# Main.net
KiCad netlist of a schematic drawn in Altium Designer
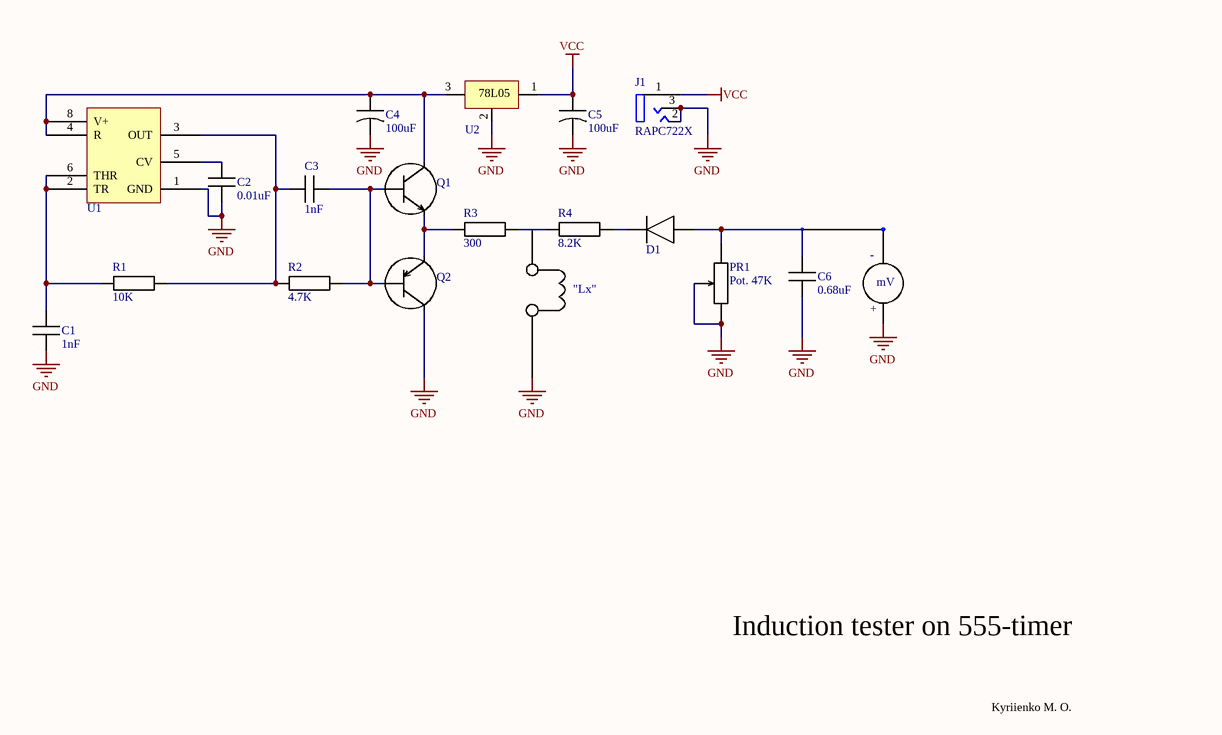
[diagram p0: Main.SchDoc]

(export (version "E")
  (design (tool "Eeschema 10.0.6"))
  (components
    (comp (ref "C1")
      (value "1nF")
      (footprint "Ceramica")
      (description "CAP CER 1000PF 1.5KV X7R RADIAL")
      (fields
        (field (name "MANUFACTURER") "KEMET")
        (field (name "MANUFACTURER PART NUMBER") "C322C102KFR5TA")
      )
      (libsource (lib "ComponentsLibrary") (part "C322C102KFR5TA"))
    )
    (comp (ref "C2")
      (value "0.01uF")
      (footprint "Ceramica")
      (description "Cap Ceramic 0.01uF 100V X7R 10% Radial 2.5mm 125C Bulk")
      (fields
        (field (name "MANUFACTURER") "Vishay BCcomponents")
        (field (name "MANUFACTURER PART NUMBER") "K103K15X7RH53L2")
      )
      (libsource (lib "ComponentsLibrary") (part "K103K15X7RH53L2"))
    )
    (comp (ref "C3")
      (value "1nF")
      (footprint "Ceramica")
      (description "CAP CER 1000PF 1.5KV X7R RADIAL")
      (fields
        (field (name "MANUFACTURER") "KEMET")
        (field (name "MANUFACTURER PART NUMBER") "C322C102KFR5TA")
      )
      (libsource (lib "ComponentsLibrary") (part "C322C102KFR5TA"))
    )
    (comp (ref "C4")
      (value "100uF")
      (footprint "Electrolytic")
      (description "Cap Aluminum Lytic 100uF 16V 20% (6.3 X 11mm) Radial 2.5mm 175mA 2000h 105C Ammo Pack")
      (fields
        (field (name "MANUFACTURER") "Nichicon")
        (field (name "MANUFACTURER PART NUMBER") "UPJ1C101MED1TD")
      )
      (libsource (lib "ComponentsLibrary") (part "UPJ1C101MED1TD"))
    )
    (comp (ref "C5")
      (value "100uF")
      (footprint "Electrolytic")
      (description "Cap Aluminum Lytic 100uF 16V 20% (6.3 X 11mm) Radial 2.5mm 175mA 2000h 105C Ammo Pack")
      (fields
        (field (name "MANUFACTURER") "Nichicon")
        (field (name "MANUFACTURER PART NUMBER") "UPJ1C101MED1TD")
      )
      (libsource (lib "ComponentsLibrary") (part "UPJ1C101MED1TD"))
    )
    (comp (ref "C6")
      (value "0.68uF")
      (footprint "Ceramica")
      (description "Capacitor Ceramic 0.68uF 50V X7R 10% 5mm Bulk")
      (fields
        (field (name "MANUFACTURER") "TDK")
        (field (name "MANUFACTURER PART NUMBER") "FA24X7R1H684KRU00")
      )
      (libsource (lib "ComponentsLibrary") (part "FA24X7R1H684KRU00"))
    )
    (comp (ref "D1")
      (value "Diode")
      (footprint "Diode")
      (description "Diode Ultra Fast Recovery Rectifier 100 Volt 0.3A 2-Pin DO-3")
      (fields
        (field (name "MANUFACTURER") "ON Semiconductor / Fairchild")
        (field (name "MANUFACTURER PART NUMBER") "1N4148")
      )
      (libsource (lib "ComponentsLibrary") (part "1N4148"))
    )
    (comp (ref "J1")
      (value "Conn_Switchcraft_RAPC722X_eec")
      (footprint "Switchcraft_RAPC722X_0")
      (description "CONN PWR JACK 2X5.5MM SOLDER")
      (fields
        (field (name "PART NUMBER") "RAPC722X")
        (field (name "MANUFACTURER") "Switchcraft")
        (field (name "MOUSER PART NUMBER") "502-RAPC722X")
      )
      (libsource (lib "Conn_Switchcraft_RAPC722X_eec") (part "Conn_Switchcraft_RAPC722X_eec"))
    )
    (comp (ref "PR1")
      (value "Pot. 47K")
      (footprint "Portentiometr")
      (description "Potentiometers 23E 47KA 10% 6.35X16FL B8")
      (fields
        (field (name "MANUFACTURER") "TE Connectivity")
        (field (name "MANUFACTURER PART NUMBER") "23ESA473KMF16N")
      )
      (libsource (lib "ComponentsLibrary") (part "23ESA473KMF16N"))
    )
    (comp (ref "Q1")
      (value "npn")
      (footprint "TO-92")
      (fields
        (field (name "MANUFACTURER") "ON Semiconductor / Fairchild")
        (field (name "MANUFACTURER PART NUMBER") "BC547B")
        (field (name "VOLTAGE") "40V")
      )
      (libsource (lib "ComponentsLibrary") (part "BC547B"))
    )
    (comp (ref "Q2")
      (value "pnp")
      (footprint "TO-92")
      (description "TRANS PNP 45V 0.2A TO-92")
      (fields
        (field (name "MANUFACTURER") "ON Semiconductor / Fairchild")
        (field (name "MANUFACTURER PART NUMBER") "KSA539YTA")
      )
      (libsource (lib "ComponentsLibrary") (part "KSA539YTA"))
    )
    (comp (ref "R1")
      (value "10K")
      (footprint "RESISTOR")
      (description "Carbon Film Resistors - Through Hole 10KOhm 1W 500PPM")
      (fields
        (field (name "MANUFACTURER") "TE Connectivity")
        (field (name "MANUFACTURER PART NUMBER") "CFR100J10K")
      )
      (libsource (lib "ComponentsLibrary") (part "CFR100J10K"))
    )
    (comp (ref "R2")
      (value "4.7K")
      (footprint "RESISTOR")
      (description "Res Carbon Film 4.7K Ohm 5% 0.25W(1/4W) -450ppm/C to 350ppm/C Conformal Coated AXL T/R")
      (fields
        (field (name "MANUFACTURER") "KOA Speer")
        (field (name "MANUFACTURER PART NUMBER") "CFS1/4CT52R472J")
      )
      (libsource (lib "ComponentsLibrary") (part "CFS1/4CT52R472J"))
    )
    (comp (ref "R3")
      (value "300")
      (footprint "RESISTOR")
      (description "RES 300 OHM 1W 5% AXIAL")
      (fields
        (field (name "MANUFACTURER") "Yageo")
        (field (name "MANUFACTURER PART NUMBER") "RSF100JB-73-300R")
      )
      (libsource (lib "ComponentsLibrary") (part "RSF100JB-73-300R"))
    )
    (comp (ref "R4")
      (value "8.2K")
      (footprint "RESISTOR")
      (description "RES 8.2K OHM 1/4W 5% AXIAL")
      (fields
        (field (name "MANUFACTURER") "Stackpole Electronics")
        (field (name "MANUFACTURER PART NUMBER") "CF14JA8K20")
      )
      (libsource (lib "ComponentsLibrary") (part "CF14JA8K20"))
    )
    (comp (ref "U1")
      (value "timer 555")
      (footprint "DIP8")
      (description "Standard Timer Single 8-Pin PDIP Tube")
      (fields
        (field (name "MANUFACTURER") "Texas Instruments")
        (field (name "MANUFACTURER PART NUMBER") "NE555P")
      )
      (libsource (lib "ComponentsLibrary") (part "NE555P"))
    )
    (comp (ref "U2")
      (value "78L05")
      (footprint "TO-92")
      (description "Standard Regulator Pos 5V 0.1A 3-Pin TO-92 Bag")
      (fields
        (field (name "MANUFACTURER") "STMicroelectronics")
        (field (name "MANUFACTURER PART NUMBER") "L78L05ACZ")
      )
      (libsource (lib "ComponentsLibrary") (part "L78L05ACZ"))
    )
  )
  (nets
    (net (code "1") (name "GND") (class "Default")
      (node (ref "C1") (pin "2") (pinfunction "2_2") (pintype "passive"))
      (node (ref "C2") (pin "2") (pinfunction "2_2") (pintype "passive"))
      (node (ref "C4") (pin "2") (pinfunction "2_2") (pintype "passive"))
      (node (ref "C5") (pin "2") (pinfunction "2_2") (pintype "passive"))
      (node (ref "C6") (pin "2") (pinfunction "2_2") (pintype "passive"))
      (node (ref "J1") (pin "2") (pinfunction "DETECT_2") (pintype "passive"))
      (node (ref "J1") (pin "3") (pinfunction "CENTER_TIP_3") (pintype "passive"))
      (node (ref "PR1") (pin "2") (pinfunction "OUT_2") (pintype "passive"))
      (node (ref "PR1") (pin "3") (pinfunction "GND_3") (pintype "passive"))
      (node (ref "Q2") (pin "3") (pinfunction "C_3") (pintype "passive"))
      (node (ref "U1") (pin "1") (pinfunction "GND_1") (pintype "passive"))
      (node (ref "U2") (pin "2") (pinfunction "GND_2") (pintype "passive"))
    )
    (net (code "2") (name "Net-(D1-Anode)") (class "Default")
      (node (ref "C6") (pin "1") (pinfunction "1_1") (pintype "passive"))
      (node (ref "D1") (pin "1") (pinfunction "Anode_1") (pintype "passive"))
      (node (ref "PR1") (pin "1") (pinfunction "IN_1") (pintype "passive"))
    )
    (net (code "3") (name "Net-(D1-Kathode)") (class "Default")
      (node (ref "D1") (pin "2") (pinfunction "Kathode_2") (pintype "passive"))
      (node (ref "R4") (pin "1") (pinfunction "1_1") (pintype "passive"))
    )
    (net (code "4") (name "Net-(Q1-B)") (class "Default")
      (node (ref "C3") (pin "1") (pinfunction "1_1") (pintype "passive"))
      (node (ref "Q1") (pin "2") (pinfunction "B_2") (pintype "passive"))
      (node (ref "Q2") (pin "2") (pinfunction "B_2") (pintype "passive"))
      (node (ref "R2") (pin "1") (pinfunction "1_1") (pintype "passive"))
    )
    (net (code "5") (name "Net-(Q1-C)") (class "Default")
      (node (ref "C4") (pin "1") (pinfunction "1_1") (pintype "passive"))
      (node (ref "Q1") (pin "3") (pinfunction "C_3") (pintype "passive"))
      (node (ref "U1") (pin "4") (pinfunction "R_4") (pintype "passive"))
      (node (ref "U1") (pin "8") (pinfunction "V+_8") (pintype "passive"))
      (node (ref "U2") (pin "3") (pinfunction "IN_3") (pintype "passive"))
    )
    (net (code "6") (name "Net-(Q1-E)") (class "Default")
      (node (ref "Q1") (pin "1") (pinfunction "E_1") (pintype "passive"))
      (node (ref "Q2") (pin "1") (pinfunction "E_1") (pintype "passive"))
      (node (ref "R3") (pin "2") (pinfunction "2_2") (pintype "passive"))
    )
    (net (code "7") (name "Net-(R3-Pad1)") (class "Default")
      (node (ref "R3") (pin "1") (pinfunction "1_1") (pintype "passive"))
      (node (ref "R4") (pin "2") (pinfunction "2_2") (pintype "passive"))
    )
    (net (code "8") (name "Net-(U1-CV)") (class "Default")
      (node (ref "C2") (pin "1") (pinfunction "1_1") (pintype "passive"))
      (node (ref "U1") (pin "5") (pinfunction "CV_5") (pintype "passive"))
    )
    (net (code "9") (name "Net-(U1-OUT)") (class "Default")
      (node (ref "C3") (pin "2") (pinfunction "2_2") (pintype "passive"))
      (node (ref "R1") (pin "1") (pinfunction "1_1") (pintype "passive"))
      (node (ref "R2") (pin "2") (pinfunction "2_2") (pintype "passive"))
      (node (ref "U1") (pin "3") (pinfunction "OUT_3") (pintype "passive"))
    )
    (net (code "10") (name "Net-(U1-THR)") (class "Default")
      (node (ref "C1") (pin "1") (pinfunction "1_1") (pintype "passive"))
      (node (ref "R1") (pin "2") (pinfunction "2_2") (pintype "passive"))
      (node (ref "U1") (pin "2") (pinfunction "TR_2") (pintype "passive"))
      (node (ref "U1") (pin "6") (pinfunction "THR_6") (pintype "passive"))
    )
    (net (code "11") (name "VCC") (class "Default")
      (node (ref "C5") (pin "1") (pinfunction "1_1") (pintype "passive"))
      (node (ref "J1") (pin "1") (pinfunction "SLEEVE_1") (pintype "passive"))
      (node (ref "U2") (pin "1") (pinfunction "OUT_1") (pintype "passive"))
    )
  )
)
